# ProtectionADC.net
KiCad netlist of a schematic drawn in Altium Designer
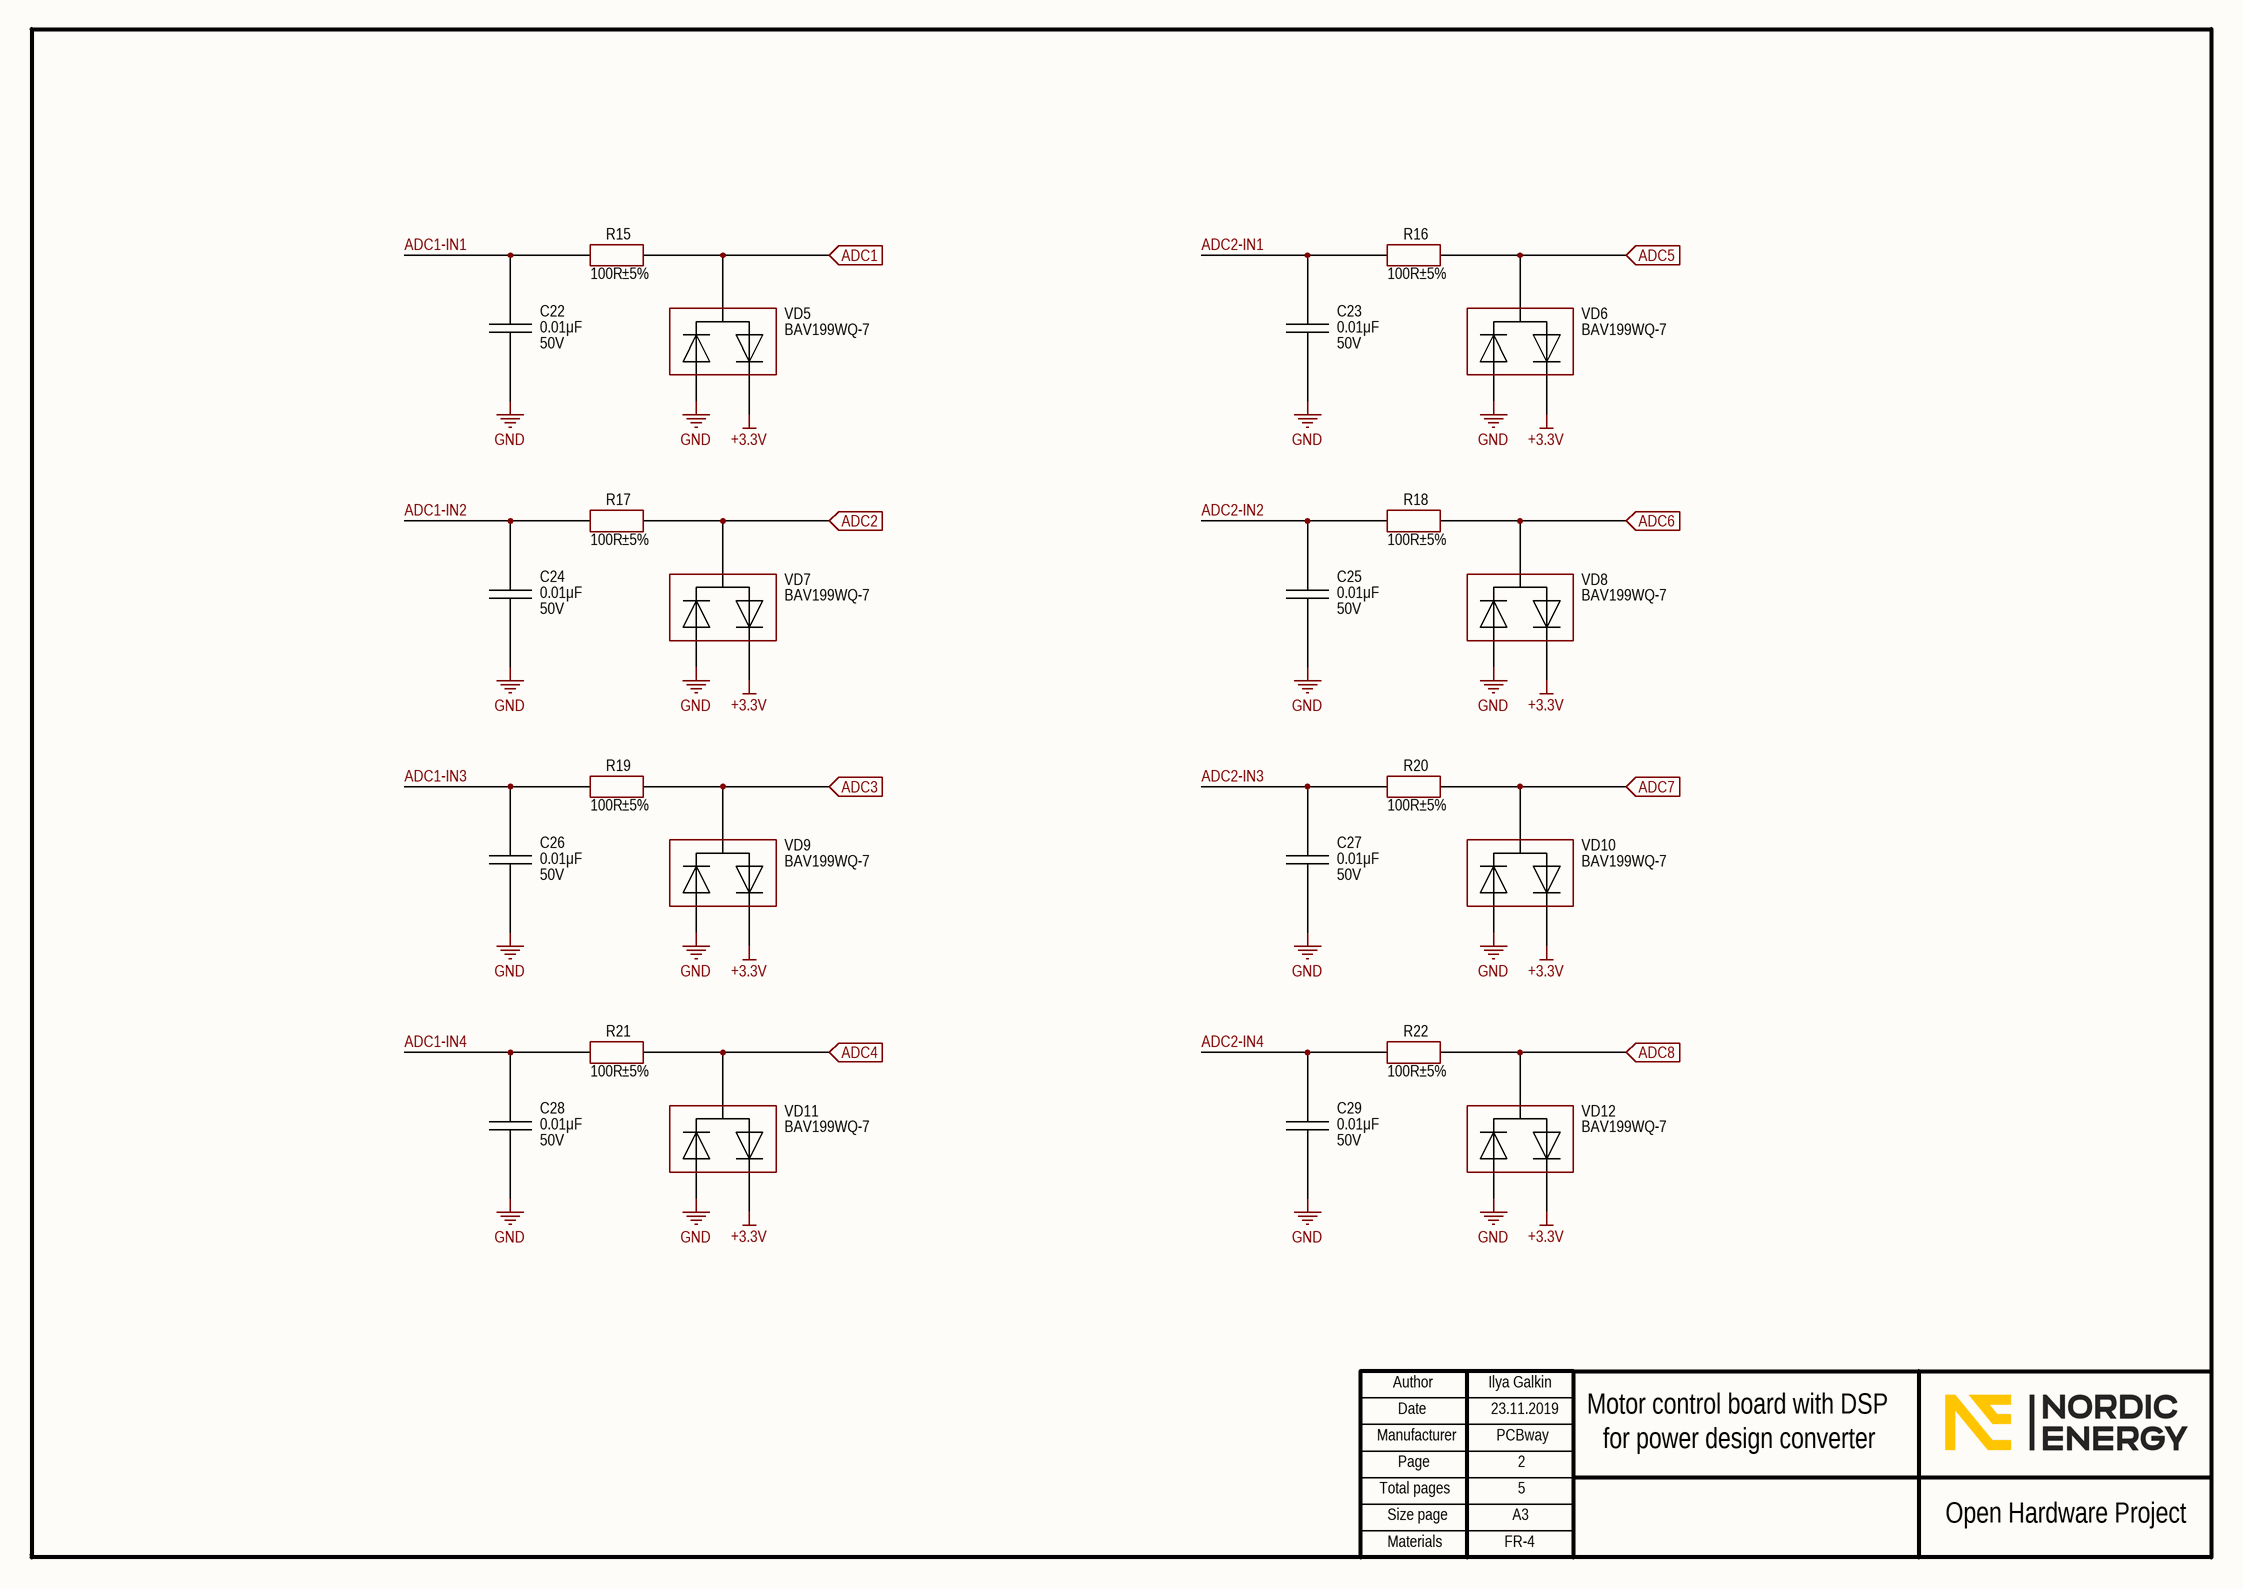
[diagram p0: ProtectionADC.SchDoc]

(export (version "E")
  (design (tool "Eeschema 10.0.6"))
  (components
    (comp (ref "C22")
      (value "0.01μF")
      (footprint "CAP: 0603")
      (fields
        (field (name "MANUFACTURER") "Samsung")
        (field (name "PARTNUMBER") "CL10B103KB8NNNC")
        (field (name "VALUEMANUFACTURERPARTNUMBER") "Ceramic capacitor, 0.01μF, X7R, ±10%, 50V, 0603, -55...+125°C")
        (field (name "VOLTAGE") "50V")
      )
      (libsource (lib "Capacitor") (part "Ceramic_0603"))
    )
    (comp (ref "C23")
      (value "0.01μF")
      (footprint "CAP: 0603")
      (fields
        (field (name "MANUFACTURER") "Samsung")
        (field (name "PARTNUMBER") "CL10B103KB8NNNC")
        (field (name "VALUEMANUFACTURERPARTNUMBER") "Ceramic capacitor, 0.01μF, X7R, ±10%, 50V, 0603, -55...+125°C")
        (field (name "VOLTAGE") "50V")
      )
      (libsource (lib "Capacitor") (part "Ceramic_0603"))
    )
    (comp (ref "C24")
      (value "0.01μF")
      (footprint "CAP: 0603")
      (fields
        (field (name "MANUFACTURER") "Samsung")
        (field (name "PARTNUMBER") "CL10B103KB8NNNC")
        (field (name "VALUEMANUFACTURERPARTNUMBER") "Ceramic capacitor, 0.01μF, X7R, ±10%, 50V, 0603, -55...+125°C")
        (field (name "VOLTAGE") "50V")
      )
      (libsource (lib "Capacitor") (part "Ceramic_0603"))
    )
    (comp (ref "C25")
      (value "0.01μF")
      (footprint "CAP: 0603")
      (fields
        (field (name "MANUFACTURER") "Samsung")
        (field (name "PARTNUMBER") "CL10B103KB8NNNC")
        (field (name "VALUEMANUFACTURERPARTNUMBER") "Ceramic capacitor, 0.01μF, X7R, ±10%, 50V, 0603, -55...+125°C")
        (field (name "VOLTAGE") "50V")
      )
      (libsource (lib "Capacitor") (part "Ceramic_0603"))
    )
    (comp (ref "C26")
      (value "0.01μF")
      (footprint "CAP: 0603")
      (fields
        (field (name "MANUFACTURER") "Samsung")
        (field (name "PARTNUMBER") "CL10B103KB8NNNC")
        (field (name "VALUEMANUFACTURERPARTNUMBER") "Ceramic capacitor, 0.01μF, X7R, ±10%, 50V, 0603, -55...+125°C")
        (field (name "VOLTAGE") "50V")
      )
      (libsource (lib "Capacitor") (part "Ceramic_0603"))
    )
    (comp (ref "C27")
      (value "0.01μF")
      (footprint "CAP: 0603")
      (fields
        (field (name "MANUFACTURER") "Samsung")
        (field (name "PARTNUMBER") "CL10B103KB8NNNC")
        (field (name "VALUEMANUFACTURERPARTNUMBER") "Ceramic capacitor, 0.01μF, X7R, ±10%, 50V, 0603, -55...+125°C")
        (field (name "VOLTAGE") "50V")
      )
      (libsource (lib "Capacitor") (part "Ceramic_0603"))
    )
    (comp (ref "C28")
      (value "0.01μF")
      (footprint "CAP: 0603")
      (fields
        (field (name "MANUFACTURER") "Samsung")
        (field (name "PARTNUMBER") "CL10B103KB8NNNC")
        (field (name "VALUEMANUFACTURERPARTNUMBER") "Ceramic capacitor, 0.01μF, X7R, ±10%, 50V, 0603, -55...+125°C")
        (field (name "VOLTAGE") "50V")
      )
      (libsource (lib "Capacitor") (part "Ceramic_0603"))
    )
    (comp (ref "C29")
      (value "0.01μF")
      (footprint "CAP: 0603")
      (fields
        (field (name "MANUFACTURER") "Samsung")
        (field (name "PARTNUMBER") "CL10B103KB8NNNC")
        (field (name "VALUEMANUFACTURERPARTNUMBER") "Ceramic capacitor, 0.01μF, X7R, ±10%, 50V, 0603, -55...+125°C")
        (field (name "VOLTAGE") "50V")
      )
      (libsource (lib "Capacitor") (part "Ceramic_0603"))
    )
    (comp (ref "R15")
      (value "100R")
      (footprint "RES: 0603")
      (fields
        (field (name "MANUFACTURER") "Yageo")
        (field (name "PARTNUMBER") "RC0603JR-07100RL")
        (field (name "VALUEMANUFACTURERPARTNUMBER") "Resistor film, 100R, ±5%, 0603, 0.1W, -55...+125°C")
        (field (name "TOLERANCE") "±5%")
      )
      (libsource (lib "Resistor") (part "Resistor_0603"))
    )
    (comp (ref "R16")
      (value "100R")
      (footprint "RES: 0603")
      (fields
        (field (name "MANUFACTURER") "Yageo")
        (field (name "PARTNUMBER") "RC0603JR-07100RL")
        (field (name "VALUEMANUFACTURERPARTNUMBER") "Resistor film, 100R, ±5%, 0603, 0.1W, -55...+125°C")
        (field (name "TOLERANCE") "±5%")
      )
      (libsource (lib "Resistor") (part "Resistor_0603"))
    )
    (comp (ref "R17")
      (value "100R")
      (footprint "RES: 0603")
      (fields
        (field (name "MANUFACTURER") "Yageo")
        (field (name "PARTNUMBER") "RC0603JR-07100RL")
        (field (name "VALUEMANUFACTURERPARTNUMBER") "Resistor film, 100R, ±5%, 0603, 0.1W, -55...+125°C")
        (field (name "TOLERANCE") "±5%")
      )
      (libsource (lib "Resistor") (part "Resistor_0603"))
    )
    (comp (ref "R18")
      (value "100R")
      (footprint "RES: 0603")
      (fields
        (field (name "MANUFACTURER") "Yageo")
        (field (name "PARTNUMBER") "RC0603JR-07100RL")
        (field (name "VALUEMANUFACTURERPARTNUMBER") "Resistor film, 100R, ±5%, 0603, 0.1W, -55...+125°C")
        (field (name "TOLERANCE") "±5%")
      )
      (libsource (lib "Resistor") (part "Resistor_0603"))
    )
    (comp (ref "R19")
      (value "100R")
      (footprint "RES: 0603")
      (fields
        (field (name "MANUFACTURER") "Yageo")
        (field (name "PARTNUMBER") "RC0603JR-07100RL")
        (field (name "VALUEMANUFACTURERPARTNUMBER") "Resistor film, 100R, ±5%, 0603, 0.1W, -55...+125°C")
        (field (name "TOLERANCE") "±5%")
      )
      (libsource (lib "Resistor") (part "Resistor_0603"))
    )
    (comp (ref "R20")
      (value "100R")
      (footprint "RES: 0603")
      (fields
        (field (name "MANUFACTURER") "Yageo")
        (field (name "PARTNUMBER") "RC0603JR-07100RL")
        (field (name "VALUEMANUFACTURERPARTNUMBER") "Resistor film, 100R, ±5%, 0603, 0.1W, -55...+125°C")
        (field (name "TOLERANCE") "±5%")
      )
      (libsource (lib "Resistor") (part "Resistor_0603"))
    )
    (comp (ref "R21")
      (value "100R")
      (footprint "RES: 0603")
      (fields
        (field (name "MANUFACTURER") "Yageo")
        (field (name "PARTNUMBER") "RC0603JR-07100RL")
        (field (name "VALUEMANUFACTURERPARTNUMBER") "Resistor film, 100R, ±5%, 0603, 0.1W, -55...+125°C")
        (field (name "TOLERANCE") "±5%")
      )
      (libsource (lib "Resistor") (part "Resistor_0603"))
    )
    (comp (ref "R22")
      (value "100R")
      (footprint "RES: 0603")
      (fields
        (field (name "MANUFACTURER") "Yageo")
        (field (name "PARTNUMBER") "RC0603JR-07100RL")
        (field (name "VALUEMANUFACTURERPARTNUMBER") "Resistor film, 100R, ±5%, 0603, 0.1W, -55...+125°C")
        (field (name "TOLERANCE") "±5%")
      )
      (libsource (lib "Resistor") (part "Resistor_0603"))
    )
    (comp (ref "VD5")
      (value "~")
      (footprint "SC-70")
      (fields
        (field (name "MANUFACTURER") "Diodes Incorporated")
        (field (name "VALUEMANUFACTURERPARTNUMBER") "Diode array, 85V, 140mA, 1.1V, 3us, SC-70, -65...+150°C")
        (field (name "VOLTAGE") "85V")
        (field (name "PARTNUMBER") "BAV199WQ-7")
      )
      (libsource (lib "Diode") (part "Diode_array"))
    )
    (comp (ref "VD6")
      (value "~")
      (footprint "SC-70")
      (fields
        (field (name "MANUFACTURER") "Diodes Incorporated")
        (field (name "VALUEMANUFACTURERPARTNUMBER") "Diode array, 85V, 140mA, 1.1V, 3us, SC-70, -65...+150°C")
        (field (name "VOLTAGE") "85V")
        (field (name "PARTNUMBER") "BAV199WQ-7")
      )
      (libsource (lib "Diode") (part "Diode_array"))
    )
    (comp (ref "VD7")
      (value "~")
      (footprint "SC-70")
      (fields
        (field (name "MANUFACTURER") "Diodes Incorporated")
        (field (name "VALUEMANUFACTURERPARTNUMBER") "Diode array, 85V, 140mA, 1.1V, 3us, SC-70, -65...+150°C")
        (field (name "VOLTAGE") "85V")
        (field (name "PARTNUMBER") "BAV199WQ-7")
      )
      (libsource (lib "Diode") (part "Diode_array"))
    )
    (comp (ref "VD8")
      (value "~")
      (footprint "SC-70")
      (fields
        (field (name "MANUFACTURER") "Diodes Incorporated")
        (field (name "VALUEMANUFACTURERPARTNUMBER") "Diode array, 85V, 140mA, 1.1V, 3us, SC-70, -65...+150°C")
        (field (name "VOLTAGE") "85V")
        (field (name "PARTNUMBER") "BAV199WQ-7")
      )
      (libsource (lib "Diode") (part "Diode_array"))
    )
    (comp (ref "VD9")
      (value "~")
      (footprint "SC-70")
      (fields
        (field (name "MANUFACTURER") "Diodes Incorporated")
        (field (name "VALUEMANUFACTURERPARTNUMBER") "Diode array, 85V, 140mA, 1.1V, 3us, SC-70, -65...+150°C")
        (field (name "VOLTAGE") "85V")
        (field (name "PARTNUMBER") "BAV199WQ-7")
      )
      (libsource (lib "Diode") (part "Diode_array"))
    )
    (comp (ref "VD10")
      (value "~")
      (footprint "SC-70")
      (fields
        (field (name "MANUFACTURER") "Diodes Incorporated")
        (field (name "VALUEMANUFACTURERPARTNUMBER") "Diode array, 85V, 140mA, 1.1V, 3us, SC-70, -65...+150°C")
        (field (name "VOLTAGE") "85V")
        (field (name "PARTNUMBER") "BAV199WQ-7")
      )
      (libsource (lib "Diode") (part "Diode_array"))
    )
    (comp (ref "VD11")
      (value "~")
      (footprint "SC-70")
      (fields
        (field (name "MANUFACTURER") "Diodes Incorporated")
        (field (name "VALUEMANUFACTURERPARTNUMBER") "Diode array, 85V, 140mA, 1.1V, 3us, SC-70, -65...+150°C")
        (field (name "VOLTAGE") "85V")
        (field (name "PARTNUMBER") "BAV199WQ-7")
      )
      (libsource (lib "Diode") (part "Diode_array"))
    )
    (comp (ref "VD12")
      (value "~")
      (footprint "SC-70")
      (fields
        (field (name "MANUFACTURER") "Diodes Incorporated")
        (field (name "VALUEMANUFACTURERPARTNUMBER") "Diode array, 85V, 140mA, 1.1V, 3us, SC-70, -65...+150°C")
        (field (name "VOLTAGE") "85V")
        (field (name "PARTNUMBER") "BAV199WQ-7")
      )
      (libsource (lib "Diode") (part "Diode_array"))
    )
  )
  (nets
    (net (code "1") (name "+3.3V") (class "Default")
      (node (ref "VD10") (pin "2") (pinfunction "2_2") (pintype "passive"))
      (node (ref "VD11") (pin "2") (pinfunction "2_2") (pintype "passive"))
      (node (ref "VD12") (pin "2") (pinfunction "2_2") (pintype "passive"))
      (node (ref "VD5") (pin "2") (pinfunction "2_2") (pintype "passive"))
      (node (ref "VD6") (pin "2") (pinfunction "2_2") (pintype "passive"))
      (node (ref "VD7") (pin "2") (pinfunction "2_2") (pintype "passive"))
      (node (ref "VD8") (pin "2") (pinfunction "2_2") (pintype "passive"))
      (node (ref "VD9") (pin "2") (pinfunction "2_2") (pintype "passive"))
    )
    (net (code "2") (name "/ADC1") (class "Default")
      (node (ref "R15") (pin "2") (pinfunction "2_2") (pintype "passive"))
      (node (ref "VD5") (pin "3") (pinfunction "3_3") (pintype "passive"))
    )
    (net (code "3") (name "/ADC1-IN1") (class "Default")
      (node (ref "C22") (pin "2") (pinfunction "2_2") (pintype "power_in"))
      (node (ref "R15") (pin "1") (pinfunction "1_1") (pintype "passive"))
    )
    (net (code "4") (name "/ADC1-IN2") (class "Default")
      (node (ref "C24") (pin "2") (pinfunction "2_2") (pintype "power_in"))
      (node (ref "R17") (pin "1") (pinfunction "1_1") (pintype "passive"))
    )
    (net (code "5") (name "/ADC1-IN3") (class "Default")
      (node (ref "C26") (pin "2") (pinfunction "2_2") (pintype "power_in"))
      (node (ref "R19") (pin "1") (pinfunction "1_1") (pintype "passive"))
    )
    (net (code "6") (name "/ADC1-IN4") (class "Default")
      (node (ref "C28") (pin "2") (pinfunction "2_2") (pintype "power_in"))
      (node (ref "R21") (pin "1") (pinfunction "1_1") (pintype "passive"))
    )
    (net (code "7") (name "/ADC2") (class "Default")
      (node (ref "R17") (pin "2") (pinfunction "2_2") (pintype "passive"))
      (node (ref "VD7") (pin "3") (pinfunction "3_3") (pintype "passive"))
    )
    (net (code "8") (name "/ADC2-IN1") (class "Default")
      (node (ref "C23") (pin "2") (pinfunction "2_2") (pintype "power_in"))
      (node (ref "R16") (pin "1") (pinfunction "1_1") (pintype "passive"))
    )
    (net (code "9") (name "/ADC2-IN2") (class "Default")
      (node (ref "C25") (pin "2") (pinfunction "2_2") (pintype "power_in"))
      (node (ref "R18") (pin "1") (pinfunction "1_1") (pintype "passive"))
    )
    (net (code "10") (name "/ADC2-IN3") (class "Default")
      (node (ref "C27") (pin "2") (pinfunction "2_2") (pintype "power_in"))
      (node (ref "R20") (pin "1") (pinfunction "1_1") (pintype "passive"))
    )
    (net (code "11") (name "/ADC2-IN4") (class "Default")
      (node (ref "C29") (pin "2") (pinfunction "2_2") (pintype "power_in"))
      (node (ref "R22") (pin "1") (pinfunction "1_1") (pintype "passive"))
    )
    (net (code "12") (name "/ADC3") (class "Default")
      (node (ref "R19") (pin "2") (pinfunction "2_2") (pintype "passive"))
      (node (ref "VD9") (pin "3") (pinfunction "3_3") (pintype "passive"))
    )
    (net (code "13") (name "/ADC4") (class "Default")
      (node (ref "R21") (pin "2") (pinfunction "2_2") (pintype "passive"))
      (node (ref "VD11") (pin "3") (pinfunction "3_3") (pintype "passive"))
    )
    (net (code "14") (name "/ADC5") (class "Default")
      (node (ref "R16") (pin "2") (pinfunction "2_2") (pintype "passive"))
      (node (ref "VD6") (pin "3") (pinfunction "3_3") (pintype "passive"))
    )
    (net (code "15") (name "/ADC6") (class "Default")
      (node (ref "R18") (pin "2") (pinfunction "2_2") (pintype "passive"))
      (node (ref "VD8") (pin "3") (pinfunction "3_3") (pintype "passive"))
    )
    (net (code "16") (name "/ADC7") (class "Default")
      (node (ref "R20") (pin "2") (pinfunction "2_2") (pintype "passive"))
      (node (ref "VD10") (pin "3") (pinfunction "3_3") (pintype "passive"))
    )
    (net (code "17") (name "/ADC8") (class "Default")
      (node (ref "R22") (pin "2") (pinfunction "2_2") (pintype "passive"))
      (node (ref "VD12") (pin "3") (pinfunction "3_3") (pintype "passive"))
    )
    (net (code "18") (name "GND") (class "Default")
      (node (ref "C22") (pin "1") (pinfunction "1_1") (pintype "power_in"))
      (node (ref "C23") (pin "1") (pinfunction "1_1") (pintype "power_in"))
      (node (ref "C24") (pin "1") (pinfunction "1_1") (pintype "power_in"))
      (node (ref "C25") (pin "1") (pinfunction "1_1") (pintype "power_in"))
      (node (ref "C26") (pin "1") (pinfunction "1_1") (pintype "power_in"))
      (node (ref "C27") (pin "1") (pinfunction "1_1") (pintype "power_in"))
      (node (ref "C28") (pin "1") (pinfunction "1_1") (pintype "power_in"))
      (node (ref "C29") (pin "1") (pinfunction "1_1") (pintype "power_in"))
      (node (ref "VD10") (pin "1") (pinfunction "1_1") (pintype "passive"))
      (node (ref "VD11") (pin "1") (pinfunction "1_1") (pintype "passive"))
      (node (ref "VD12") (pin "1") (pinfunction "1_1") (pintype "passive"))
      (node (ref "VD5") (pin "1") (pinfunction "1_1") (pintype "passive"))
      (node (ref "VD6") (pin "1") (pinfunction "1_1") (pintype "passive"))
      (node (ref "VD7") (pin "1") (pinfunction "1_1") (pintype "passive"))
      (node (ref "VD8") (pin "1") (pinfunction "1_1") (pintype "passive"))
      (node (ref "VD9") (pin "1") (pinfunction "1_1") (pintype "passive"))
    )
  )
)
